# Pi-Kuehler.net
KiCad netlist of a schematic drawn in EAGLE
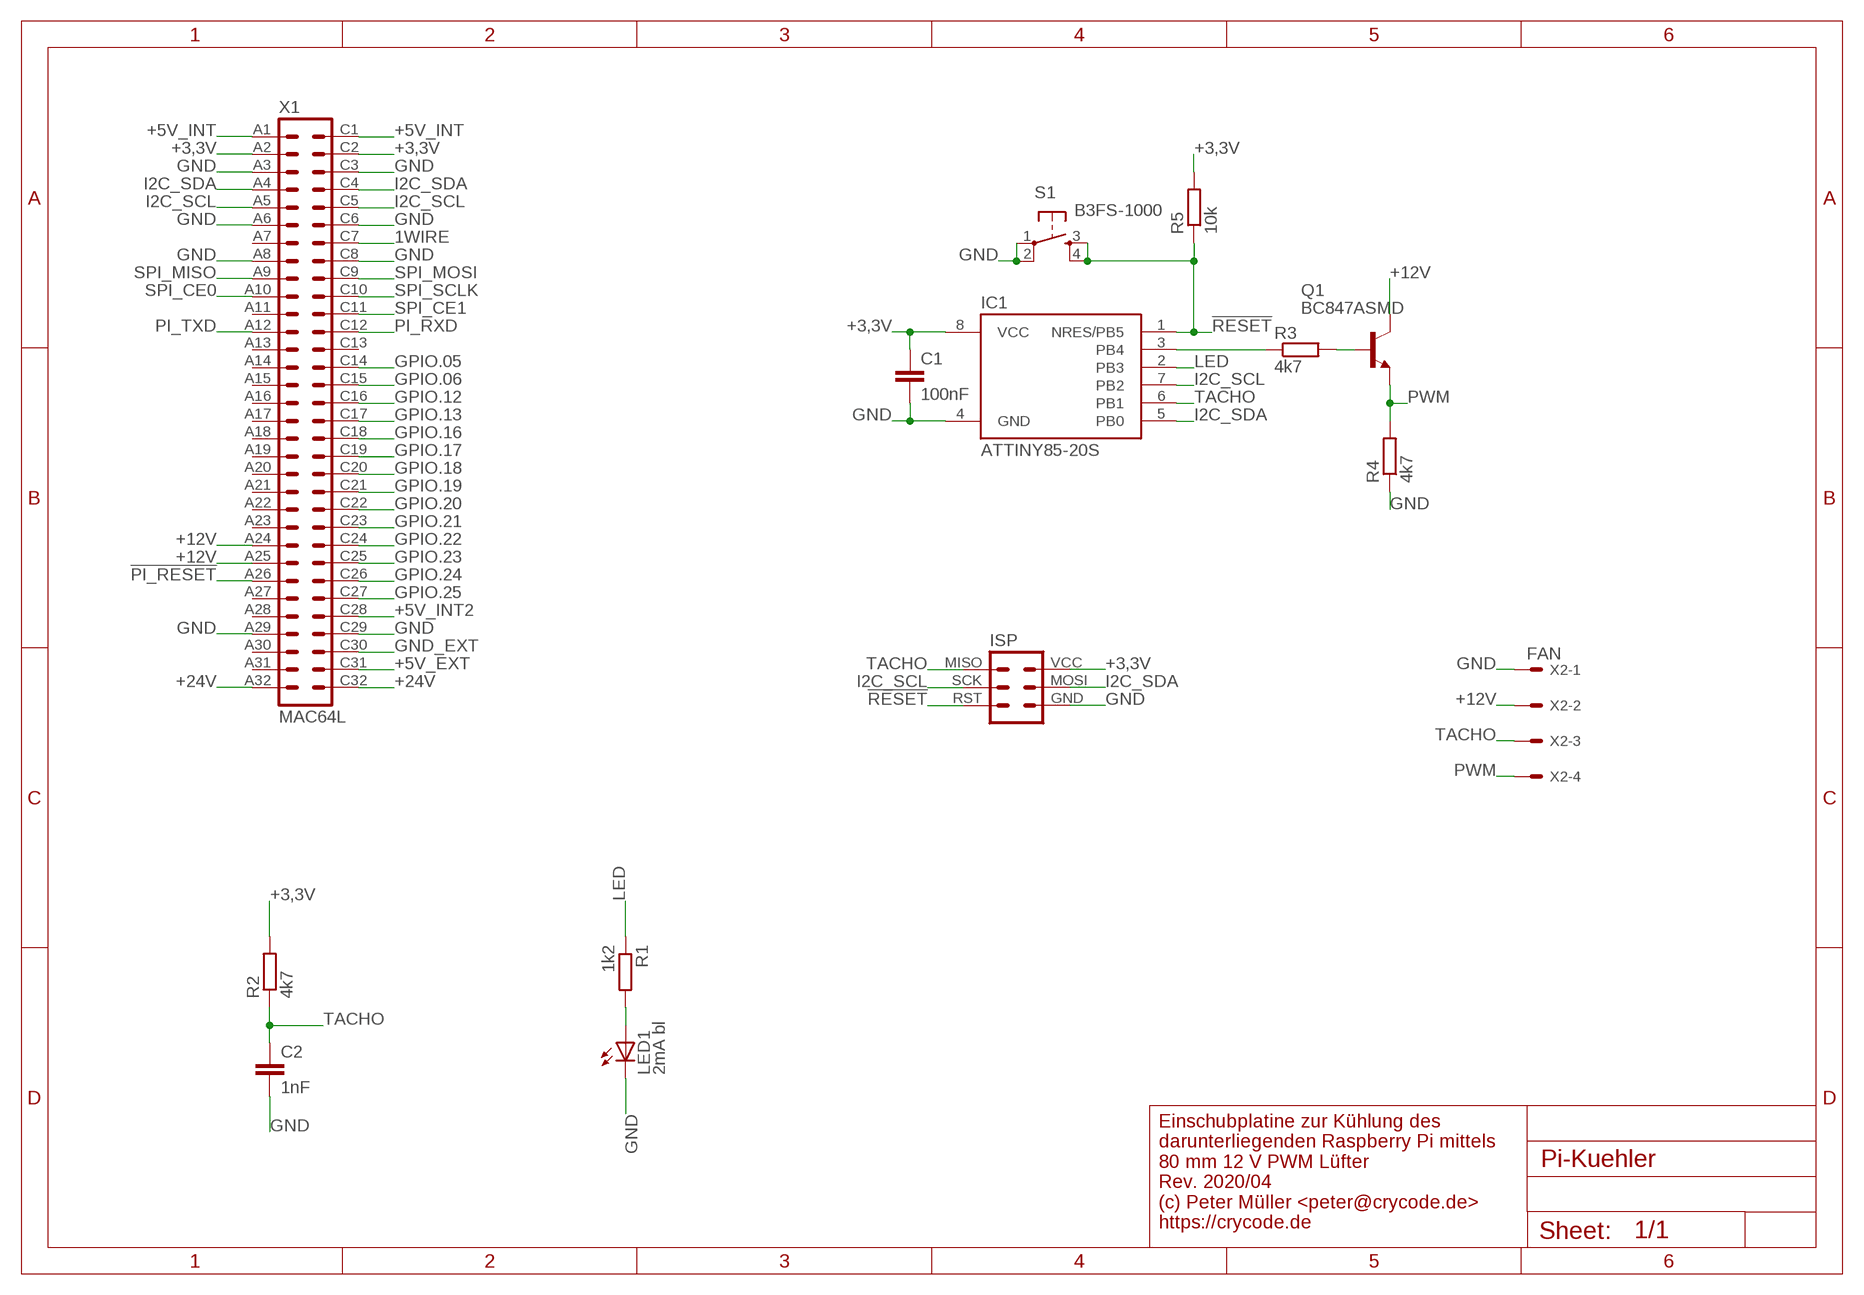
[diagram p0: schematic, sheet 1]

(export (version "E")
  (design (tool "Eeschema 10.0.6"))
  (components
    (comp (ref "C1")
      (value "100nF")
      (footprint "eagle-import:C1206")
      (libsource (lib "eagle-import") (part "C-EUC1206"))
    )
    (comp (ref "C2")
      (value "1nF")
      (footprint "eagle-import:C1206")
      (libsource (lib "eagle-import") (part "C-EUC1206"))
    )
    (comp (ref "IC1")
      (value "ATTINY85-20S")
      (footprint "eagle-import:SOIC8_EIAJ_208MIL")
      (libsource (lib "eagle-import") (part "ATTINY85S-20"))
    )
    (comp (ref "ISP")
      (value "ISPVIAS-ONLY-1.27MM")
      (footprint "eagle-import:ISP-VIAS-ONLY-1.27MM")
      (libsource (lib "eagle-import") (part "ISPVIAS-ONLY-1.27MM"))
    )
    (comp (ref "LED1")
      (value "2mA bl")
      (footprint "eagle-import:CHIPLED_1206")
      (libsource (lib "eagle-import") (part "LEDCHIPLED_1206"))
    )
    (comp (ref "Q1")
      (value "BC847ASMD")
      (footprint "eagle-import:SOT23")
      (libsource (lib "eagle-import") (part "BC847SMDA"))
    )
    (comp (ref "R1")
      (value "1k2")
      (footprint "eagle-import:R1206")
      (libsource (lib "eagle-import") (part "R-EU_R1206"))
    )
    (comp (ref "R2")
      (value "4k7")
      (footprint "eagle-import:R1206")
      (libsource (lib "eagle-import") (part "R-EU_R1206"))
    )
    (comp (ref "R3")
      (value "4k7")
      (footprint "eagle-import:R1206")
      (libsource (lib "eagle-import") (part "R-EU_R1206"))
    )
    (comp (ref "R4")
      (value "4k7")
      (footprint "eagle-import:R1206")
      (libsource (lib "eagle-import") (part "R-EU_R1206"))
    )
    (comp (ref "R5")
      (value "10k")
      (footprint "eagle-import:R1206")
      (libsource (lib "eagle-import") (part "R-EU_R1206"))
    )
    (comp (ref "S1")
      (value "B3FS-1000")
      (footprint "eagle-import:B3FS-1000")
      (libsource (lib "eagle-import") (part "B3FS-1000"))
    )
    (comp (ref "X1")
      (value "MAC64L")
      (footprint "eagle-import:MAC64L")
      (libsource (lib "eagle-import") (part "MAC64L"))
    )
    (comp (ref "X2")
      (value "FAN")
      (footprint "eagle-import:6410-04")
      (libsource (lib "eagle-import") (part "22-?-0427-2041"))
    )
  )
  (nets
    (net (code "1") (name "/+3,3V") (class "Default")
      (node (ref "C1") (pin "1") (pinfunction "1_1") (pintype "passive"))
      (node (ref "IC1") (pin "8") (pinfunction "VCC_8") (pintype "power_in"))
      (node (ref "ISP") (pin "VCC") (pinfunction "VCC_VCC") (pintype "passive"))
      (node (ref "R2") (pin "2") (pinfunction "2_2") (pintype "passive"))
      (node (ref "R5") (pin "2") (pinfunction "2_2") (pintype "passive"))
      (node (ref "X1") (pin "A2") (pinfunction "A2_A2") (pintype "passive"))
      (node (ref "X1") (pin "C2") (pinfunction "C2_C2") (pintype "passive"))
    )
    (net (code "2") (name "/+5V_EXT") (class "Default")
      (node (ref "X1") (pin "C31") (pinfunction "C31_C31") (pintype "passive"))
    )
    (net (code "3") (name "/+5V_INT") (class "Default")
      (node (ref "X1") (pin "A1") (pinfunction "A1_A1") (pintype "passive"))
      (node (ref "X1") (pin "C1") (pinfunction "C1_C1") (pintype "passive"))
    )
    (net (code "4") (name "/+5V_INT2") (class "Default")
      (node (ref "X1") (pin "C28") (pinfunction "C28_C28") (pintype "passive"))
    )
    (net (code "5") (name "/+12V") (class "Default")
      (node (ref "Q1") (pin "3") (pinfunction "C_3") (pintype "passive"))
      (node (ref "X1") (pin "A24") (pinfunction "A24_A24") (pintype "passive"))
      (node (ref "X1") (pin "A25") (pinfunction "A25_A25") (pintype "passive"))
      (node (ref "X2") (pin "2") (pinfunction "S_2") (pintype "passive"))
    )
    (net (code "6") (name "/+24V") (class "Default")
      (node (ref "X1") (pin "A32") (pinfunction "A32_A32") (pintype "passive"))
      (node (ref "X1") (pin "C32") (pinfunction "C32_C32") (pintype "passive"))
    )
    (net (code "7") (name "/1WIRE") (class "Default")
      (node (ref "X1") (pin "C7") (pinfunction "C7_C7") (pintype "passive"))
    )
    (net (code "8") (name "/GND") (class "Default")
      (node (ref "C1") (pin "2") (pinfunction "2_2") (pintype "passive"))
      (node (ref "C2") (pin "2") (pinfunction "2_2") (pintype "passive"))
      (node (ref "IC1") (pin "4") (pinfunction "GND_4") (pintype "power_in"))
      (node (ref "ISP") (pin "GND") (pinfunction "GND_GND") (pintype "passive"))
      (node (ref "LED1") (pin "C") (pinfunction "C_C") (pintype "passive"))
      (node (ref "R4") (pin "1") (pinfunction "1_1") (pintype "passive"))
      (node (ref "S1") (pin "1") (pinfunction "P_1") (pintype "passive"))
      (node (ref "S1") (pin "2") (pinfunction "P1_2") (pintype "passive"))
      (node (ref "X1") (pin "A29") (pinfunction "A29_A29") (pintype "passive"))
      (node (ref "X1") (pin "A3") (pinfunction "A3_A3") (pintype "passive"))
      (node (ref "X1") (pin "A6") (pinfunction "A6_A6") (pintype "passive"))
      (node (ref "X1") (pin "A8") (pinfunction "A8_A8") (pintype "passive"))
      (node (ref "X1") (pin "C29") (pinfunction "C29_C29") (pintype "passive"))
      (node (ref "X1") (pin "C3") (pinfunction "C3_C3") (pintype "passive"))
      (node (ref "X1") (pin "C6") (pinfunction "C6_C6") (pintype "passive"))
      (node (ref "X1") (pin "C8") (pinfunction "C8_C8") (pintype "passive"))
      (node (ref "X2") (pin "1") (pinfunction "S_1") (pintype "passive"))
    )
    (net (code "9") (name "/GND_EXT") (class "Default")
      (node (ref "X1") (pin "C30") (pinfunction "C30_C30") (pintype "passive"))
    )
    (net (code "10") (name "/GPIO.05") (class "Default")
      (node (ref "X1") (pin "C14") (pinfunction "C14_C14") (pintype "passive"))
    )
    (net (code "11") (name "/GPIO.06") (class "Default")
      (node (ref "X1") (pin "C15") (pinfunction "C15_C15") (pintype "passive"))
    )
    (net (code "12") (name "/GPIO.12") (class "Default")
      (node (ref "X1") (pin "C16") (pinfunction "C16_C16") (pintype "passive"))
    )
    (net (code "13") (name "/GPIO.13") (class "Default")
      (node (ref "X1") (pin "C17") (pinfunction "C17_C17") (pintype "passive"))
    )
    (net (code "14") (name "/GPIO.16") (class "Default")
      (node (ref "X1") (pin "C18") (pinfunction "C18_C18") (pintype "passive"))
    )
    (net (code "15") (name "/GPIO.17") (class "Default")
      (node (ref "X1") (pin "C19") (pinfunction "C19_C19") (pintype "passive"))
    )
    (net (code "16") (name "/GPIO.18") (class "Default")
      (node (ref "X1") (pin "C20") (pinfunction "C20_C20") (pintype "passive"))
    )
    (net (code "17") (name "/GPIO.19") (class "Default")
      (node (ref "X1") (pin "C21") (pinfunction "C21_C21") (pintype "passive"))
    )
    (net (code "18") (name "/GPIO.20") (class "Default")
      (node (ref "X1") (pin "C22") (pinfunction "C22_C22") (pintype "passive"))
    )
    (net (code "19") (name "/GPIO.21") (class "Default")
      (node (ref "X1") (pin "C23") (pinfunction "C23_C23") (pintype "passive"))
    )
    (net (code "20") (name "/GPIO.22") (class "Default")
      (node (ref "X1") (pin "C24") (pinfunction "C24_C24") (pintype "passive"))
    )
    (net (code "21") (name "/GPIO.23") (class "Default")
      (node (ref "X1") (pin "C25") (pinfunction "C25_C25") (pintype "passive"))
    )
    (net (code "22") (name "/GPIO.24") (class "Default")
      (node (ref "X1") (pin "C26") (pinfunction "C26_C26") (pintype "passive"))
    )
    (net (code "23") (name "/GPIO.25") (class "Default")
      (node (ref "X1") (pin "C27") (pinfunction "C27_C27") (pintype "passive"))
    )
    (net (code "24") (name "/I2C_SCL") (class "Default")
      (node (ref "IC1") (pin "7") (pinfunction "PB2_7") (pintype "bidirectional"))
      (node (ref "ISP") (pin "SCK") (pinfunction "SCK_SCK") (pintype "passive"))
      (node (ref "X1") (pin "A5") (pinfunction "A5_A5") (pintype "passive"))
      (node (ref "X1") (pin "C5") (pinfunction "C5_C5") (pintype "passive"))
    )
    (net (code "25") (name "/I2C_SDA") (class "Default")
      (node (ref "IC1") (pin "5") (pinfunction "PB0_5") (pintype "bidirectional"))
      (node (ref "ISP") (pin "MOSI") (pinfunction "MOSI_MOSI") (pintype "passive"))
      (node (ref "X1") (pin "A4") (pinfunction "A4_A4") (pintype "passive"))
      (node (ref "X1") (pin "C4") (pinfunction "C4_C4") (pintype "passive"))
    )
    (net (code "26") (name "/LED") (class "Default")
      (node (ref "IC1") (pin "2") (pinfunction "PB3_2") (pintype "bidirectional"))
      (node (ref "R1") (pin "1") (pinfunction "1_1") (pintype "passive"))
    )
    (net (code "27") (name "/PI_RXD") (class "Default")
      (node (ref "X1") (pin "C12") (pinfunction "C12_C12") (pintype "passive"))
    )
    (net (code "28") (name "/PI_TXD") (class "Default")
      (node (ref "X1") (pin "A12") (pinfunction "A12_A12") (pintype "passive"))
    )
    (net (code "29") (name "/PWM") (class "Default")
      (node (ref "Q1") (pin "2") (pinfunction "E_2") (pintype "passive"))
      (node (ref "R4") (pin "2") (pinfunction "2_2") (pintype "passive"))
      (node (ref "X2") (pin "4") (pinfunction "S_4") (pintype "passive"))
    )
    (net (code "30") (name "/SPI_CE0") (class "Default")
      (node (ref "X1") (pin "A10") (pinfunction "A10_A10") (pintype "passive"))
    )
    (net (code "31") (name "/SPI_CE1") (class "Default")
      (node (ref "X1") (pin "C11") (pinfunction "C11_C11") (pintype "passive"))
    )
    (net (code "32") (name "/SPI_MISO") (class "Default")
      (node (ref "X1") (pin "A9") (pinfunction "A9_A9") (pintype "passive"))
    )
    (net (code "33") (name "/SPI_MOSI") (class "Default")
      (node (ref "X1") (pin "C9") (pinfunction "C9_C9") (pintype "passive"))
    )
    (net (code "34") (name "/SPI_SCLK") (class "Default")
      (node (ref "X1") (pin "C10") (pinfunction "C10_C10") (pintype "passive"))
    )
    (net (code "35") (name "/TACHO") (class "Default")
      (node (ref "C2") (pin "1") (pinfunction "1_1") (pintype "passive"))
      (node (ref "IC1") (pin "6") (pinfunction "PB1_6") (pintype "bidirectional"))
      (node (ref "ISP") (pin "MISO") (pinfunction "MISO_MISO") (pintype "passive"))
      (node (ref "R2") (pin "1") (pinfunction "1_1") (pintype "passive"))
      (node (ref "X2") (pin "3") (pinfunction "S_3") (pintype "passive"))
    )
    (net (code "36") (name "/~{PI_RESET}") (class "Default")
      (node (ref "X1") (pin "A26") (pinfunction "A26_A26") (pintype "passive"))
    )
    (net (code "37") (name "/~{RESET}") (class "Default")
      (node (ref "IC1") (pin "1") (pinfunction "NRES/PB5_1") (pintype "bidirectional"))
      (node (ref "ISP") (pin "RST") (pinfunction "RST_RST") (pintype "passive"))
      (node (ref "R5") (pin "1") (pinfunction "1_1") (pintype "passive"))
      (node (ref "S1") (pin "3") (pinfunction "S_3") (pintype "passive"))
      (node (ref "S1") (pin "4") (pinfunction "S1_4") (pintype "passive"))
    )
    (net (code "38") (name "Net-(IC1-PB4)") (class "Default")
      (node (ref "IC1") (pin "3") (pinfunction "PB4_3") (pintype "bidirectional"))
      (node (ref "R3") (pin "1") (pinfunction "1_1") (pintype "passive"))
    )
    (net (code "39") (name "Net-(LED1-PadA)") (class "Default")
      (node (ref "LED1") (pin "A") (pinfunction "A_A") (pintype "passive"))
      (node (ref "R1") (pin "2") (pinfunction "2_2") (pintype "passive"))
    )
    (net (code "40") (name "Net-(Q1-B)") (class "Default")
      (node (ref "Q1") (pin "1") (pinfunction "B_1") (pintype "passive"))
      (node (ref "R3") (pin "2") (pinfunction "2_2") (pintype "passive"))
    )
    (net (code "41") (name "unconnected-(X1-PadA7)") (class "Default")
      (node (ref "X1") (pin "A7") (pinfunction "A7_A7") (pintype "passive"))
    )
    (net (code "42") (name "unconnected-(X1-PadA11)") (class "Default")
      (node (ref "X1") (pin "A11") (pinfunction "A11_A11") (pintype "passive"))
    )
    (net (code "43") (name "unconnected-(X1-PadA13)") (class "Default")
      (node (ref "X1") (pin "A13") (pinfunction "A13_A13") (pintype "passive"))
    )
    (net (code "44") (name "unconnected-(X1-PadA14)") (class "Default")
      (node (ref "X1") (pin "A14") (pinfunction "A14_A14") (pintype "passive"))
    )
    (net (code "45") (name "unconnected-(X1-PadA15)") (class "Default")
      (node (ref "X1") (pin "A15") (pinfunction "A15_A15") (pintype "passive"))
    )
    (net (code "46") (name "unconnected-(X1-PadA16)") (class "Default")
      (node (ref "X1") (pin "A16") (pinfunction "A16_A16") (pintype "passive"))
    )
    (net (code "47") (name "unconnected-(X1-PadA17)") (class "Default")
      (node (ref "X1") (pin "A17") (pinfunction "A17_A17") (pintype "passive"))
    )
    (net (code "48") (name "unconnected-(X1-PadA18)") (class "Default")
      (node (ref "X1") (pin "A18") (pinfunction "A18_A18") (pintype "passive"))
    )
    (net (code "49") (name "unconnected-(X1-PadA19)") (class "Default")
      (node (ref "X1") (pin "A19") (pinfunction "A19_A19") (pintype "passive"))
    )
    (net (code "50") (name "unconnected-(X1-PadA20)") (class "Default")
      (node (ref "X1") (pin "A20") (pinfunction "A20_A20") (pintype "passive"))
    )
    (net (code "51") (name "unconnected-(X1-PadA21)") (class "Default")
      (node (ref "X1") (pin "A21") (pinfunction "A21_A21") (pintype "passive"))
    )
    (net (code "52") (name "unconnected-(X1-PadA22)") (class "Default")
      (node (ref "X1") (pin "A22") (pinfunction "A22_A22") (pintype "passive"))
    )
    (net (code "53") (name "unconnected-(X1-PadA23)") (class "Default")
      (node (ref "X1") (pin "A23") (pinfunction "A23_A23") (pintype "passive"))
    )
    (net (code "54") (name "unconnected-(X1-PadA27)") (class "Default")
      (node (ref "X1") (pin "A27") (pinfunction "A27_A27") (pintype "passive"))
    )
    (net (code "55") (name "unconnected-(X1-PadA28)") (class "Default")
      (node (ref "X1") (pin "A28") (pinfunction "A28_A28") (pintype "passive"))
    )
    (net (code "56") (name "unconnected-(X1-PadA30)") (class "Default")
      (node (ref "X1") (pin "A30") (pinfunction "A30_A30") (pintype "passive"))
    )
    (net (code "57") (name "unconnected-(X1-PadA31)") (class "Default")
      (node (ref "X1") (pin "A31") (pinfunction "A31_A31") (pintype "passive"))
    )
    (net (code "58") (name "unconnected-(X1-PadC13)") (class "Default")
      (node (ref "X1") (pin "C13") (pinfunction "C13_C13") (pintype "passive"))
    )
  )
)
